# CPU_Control.net
KiCad netlist of a schematic drawn in Altium Designer
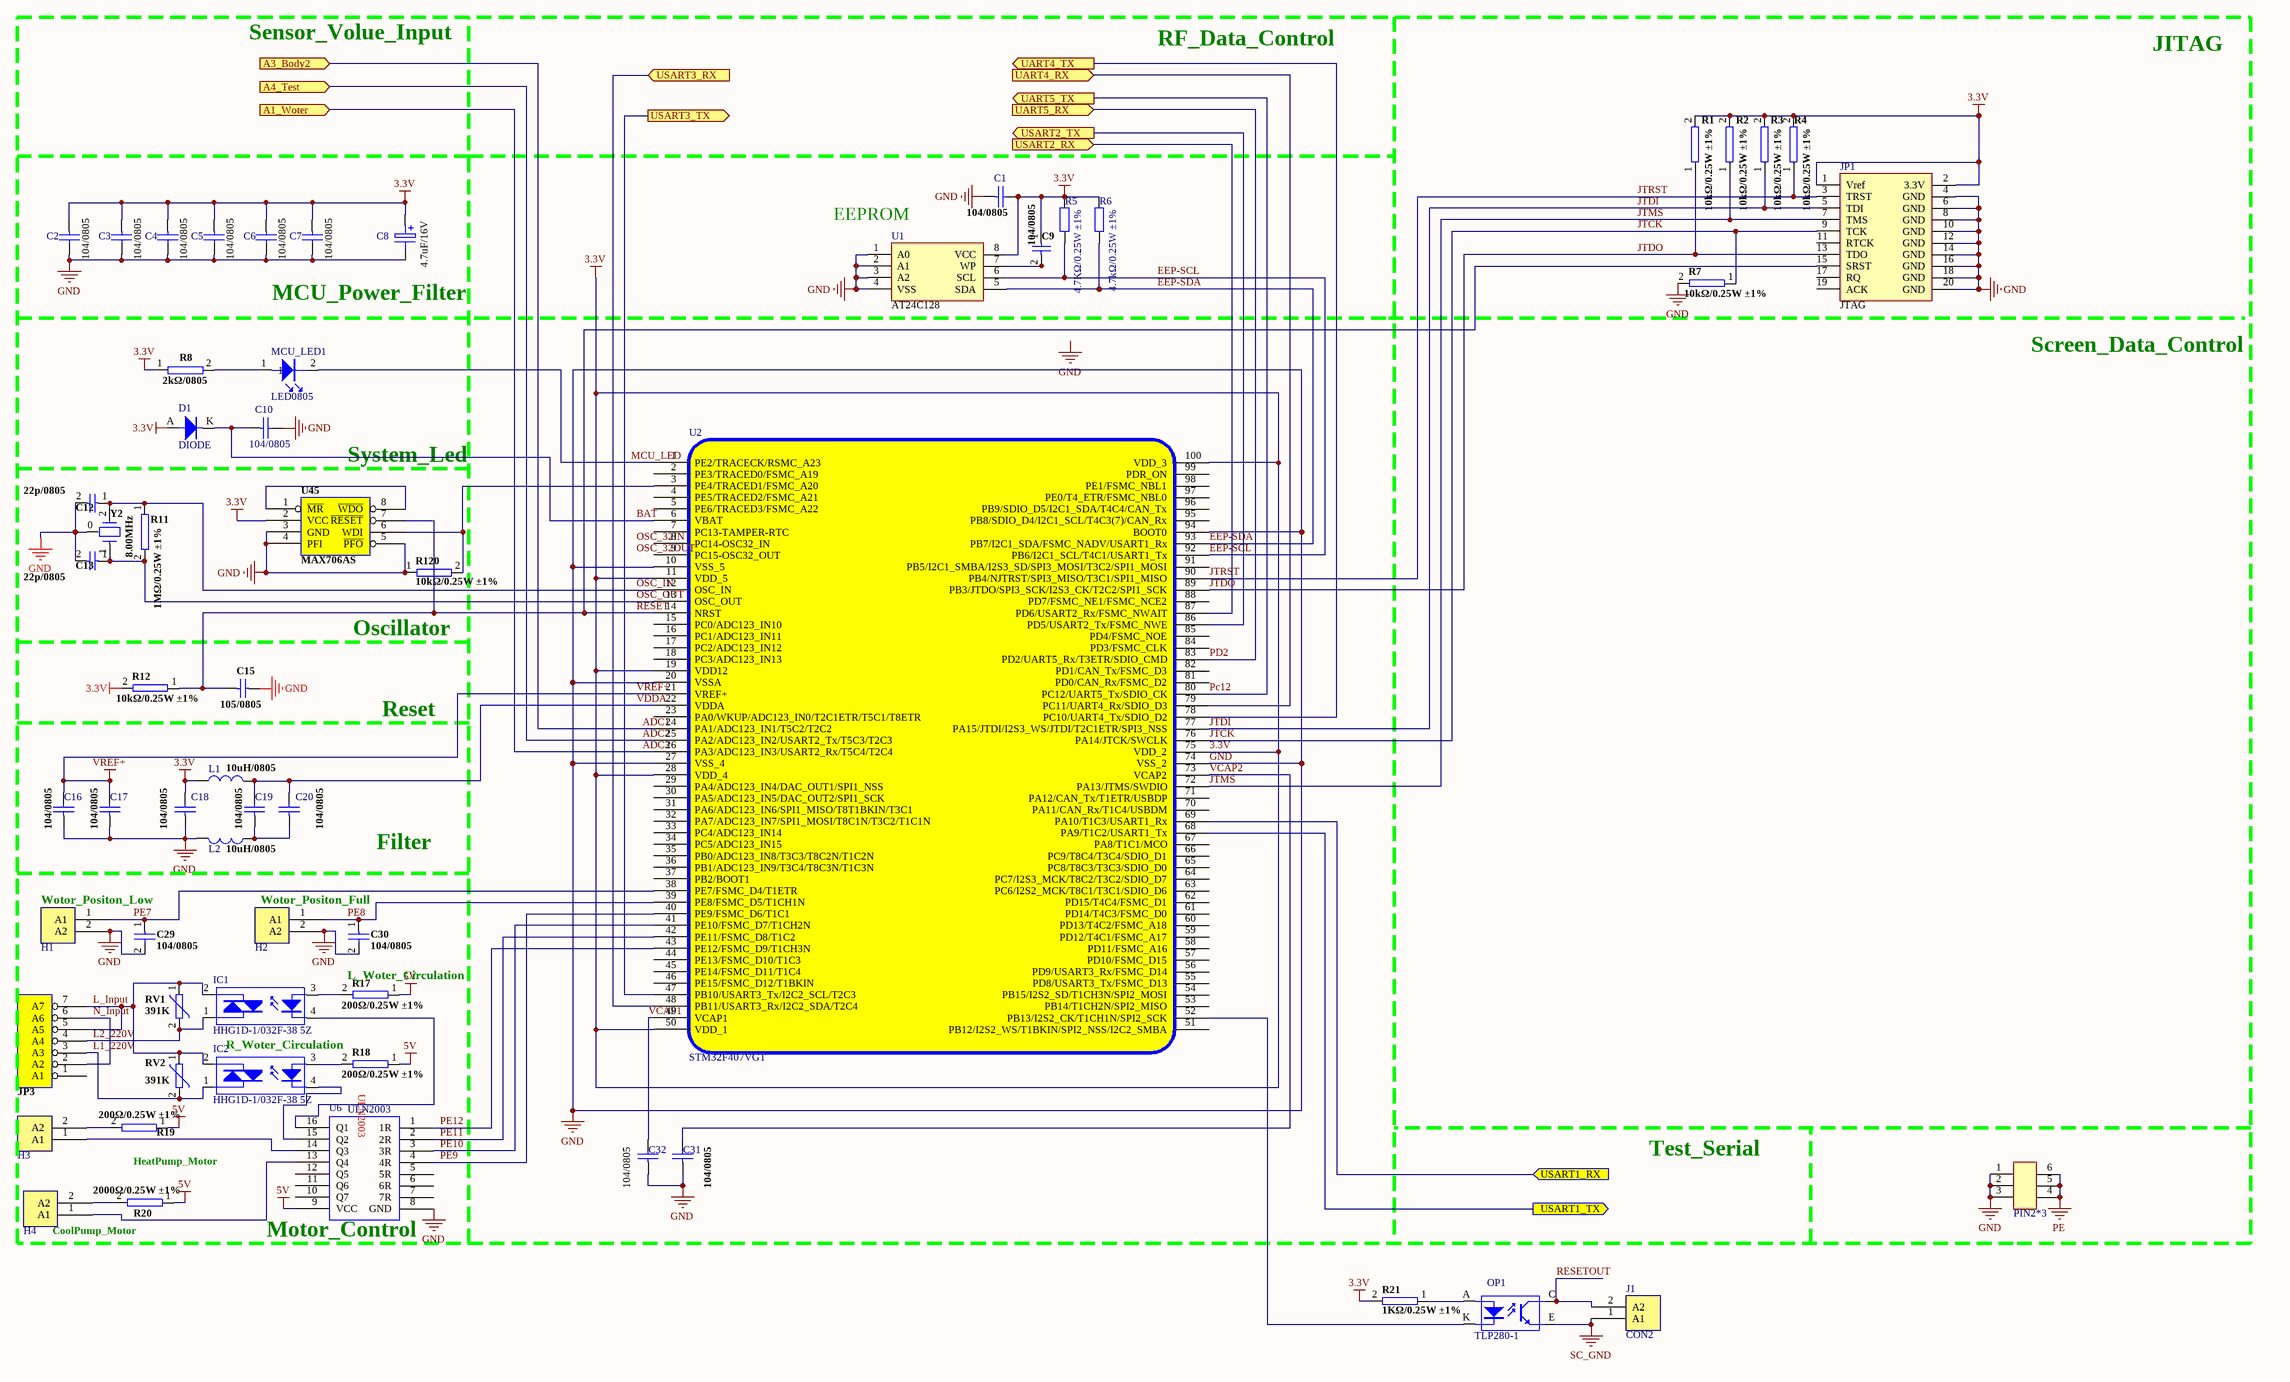
[diagram p0: CPU_Control.SchDoc]

(export (version "E")
  (design (tool "Eeschema 10.0.6"))
  (components
    (comp (ref "C1")
      (value "104/0805")
      (footprint "C0805")
      (description "贴片电容 104/25V ±1% C0805")
      (libsource (lib "*") (part "CAP"))
    )
    (comp (ref "C2")
      (value "104/0805")
      (footprint "COOLCONTROL:C0805")
      (description "贴片电容 104/25V ±1% C0805")
      (libsource (lib "*") (part "CAP"))
    )
    (comp (ref "C3")
      (value "104/0805")
      (footprint "C0805")
      (description "贴片电容 104/25V ±1% C0805")
      (libsource (lib "*") (part "CAP"))
    )
    (comp (ref "C4")
      (value "104/0805")
      (footprint "C0805")
      (description "贴片电容 104/25V ±1% C0805")
      (libsource (lib "*") (part "CAP"))
    )
    (comp (ref "C5")
      (value "104/0805")
      (footprint "C0805")
      (description "贴片电容 104/25V ±1% C0805")
      (libsource (lib "*") (part "CAP"))
    )
    (comp (ref "C6")
      (value "104/0805")
      (footprint "C0805")
      (description "贴片电容 104/25V ±1% C0805")
      (libsource (lib "*") (part "CAP"))
    )
    (comp (ref "C7")
      (value "104/0805")
      (footprint "C0805")
      (description "贴片电容 104/25V ±1% C0805")
      (libsource (lib "*") (part "CAP"))
    )
    (comp (ref "C8")
      (value "4.7uF/16V")
      (footprint "CAP5X5")
      (description "贴片钽电容 4.7uF/16V ±10% CAP5X5")
      (libsource (lib "*") (part "ELECTRO1"))
    )
    (comp (ref "C9")
      (value "104/0805")
      (footprint "C0805")
      (description "贴片电容 104/25V ±1% C0805")
      (libsource (lib "") (part "CAP_3"))
    )
    (comp (ref "C10")
      (value "104/0805")
      (footprint "C0805")
      (description "贴片电容 104/50V ±1% C0805")
      (libsource (lib "*") (part "CAP"))
    )
    (comp (ref "C12")
      (value "22p/0805")
      (footprint "C0805")
      (description "贴片电容 22pF/25V ±1% C0805")
      (libsource (lib "") (part "CAP_3"))
    )
    (comp (ref "C13")
      (value "22p/0805")
      (footprint "C0805")
      (description "贴片电容 22pF/25V ±1% C0805")
      (libsource (lib "") (part "CAP_3"))
    )
    (comp (ref "C15")
      (value "105/0805")
      (footprint "C0805")
      (description "贴片电容 105/25V ±1% C0805")
      (fields (field (name "PUBLISHER") "Altium Limited"))
      (libsource (lib "") (part "CAP_1"))
    )
    (comp (ref "C16")
      (value "104/0805")
      (footprint "C0805")
      (description "贴片电容 104/25V ±1% C0805")
      (libsource (lib "*") (part "CAP"))
    )
    (comp (ref "C17")
      (value "104/0805")
      (footprint "C0805")
      (description "贴片电容 104/25V ±1% C0805")
      (libsource (lib "*") (part "CAP"))
    )
    (comp (ref "C18")
      (value "104/0805")
      (footprint "C0805")
      (description "贴片电容 104/25V ±1% C0805")
      (libsource (lib "*") (part "CAP"))
    )
    (comp (ref "C19")
      (value "104/0805")
      (footprint "C0805")
      (description "贴片电容 104/25V ±1% C0805")
      (libsource (lib "*") (part "CAP"))
    )
    (comp (ref "C20")
      (value "104/0805")
      (footprint "C0805")
      (description "贴片电容 104/25V ±1% C0805")
      (libsource (lib "*") (part "CAP"))
    )
    (comp (ref "C29")
      (value "104/0805")
      (footprint "C0805")
      (description "贴片电容 104/25V ±1% C0805")
      (libsource (lib "") (part "CAP_2"))
    )
    (comp (ref "C30")
      (value "104/0805")
      (footprint "C0805")
      (description "贴片电容 104/25V ±1% C0805")
      (libsource (lib "") (part "CAP_2"))
    )
    (comp (ref "C31")
      (value "104/0805")
      (footprint "C0805")
      (description "贴片电容 104/25V ±1% C0805")
      (libsource (lib "*") (part "CAP"))
    )
    (comp (ref "C32")
      (value "104/0805")
      (footprint "C0805")
      (description "贴片电容 104/25V ±1% C0805")
      (libsource (lib "*") (part "CAP"))
    )
    (comp (ref "D1")
      (value "DIODE")
      (footprint "SOD123")
      (description "高速开关二极管 IN4148 1V 150mA SOD123")
      (libsource (lib "COOLCONTROL") (part "DIODE"))
    )
    (comp (ref "H1")
      (value "L_Wotor_Port")
      (footprint "XH2")
      (description "插座式端子 XH2.54-2P 250V(DC/AC) 3A")
      (libsource (lib "") (part "CON2_2"))
    )
    (comp (ref "H2")
      (value "F_Wotor_Port")
      (footprint "XH2")
      (description "插座式端子 XH2.54-2P 250V(DC/AC) 3A")
      (libsource (lib "") (part "CON2_2"))
    )
    (comp (ref "H3")
      (value "Heat_Port")
      (footprint "XH2")
      (description "插座式端子 XH2.54-2P 250V(DC/AC) 3A")
      (libsource (lib "COOLCONTROL") (part "CON2"))
    )
    (comp (ref "H4")
      (value "Cool_Port")
      (footprint "XH2")
      (description "插座式端子 XH2.54-2P 250V(DC/AC) 3A")
      (libsource (lib "COOLCONTROL") (part "CON2"))
    )
    (comp (ref "IC1")
      (value "HHG1D-1/032F-38 5Z")
      (footprint "HHG1-REALY")
      (description "固态继电器 HHG1D-1/032F-38 5Z HHG1-REALY")
      (libsource (lib "COOLCONTROL") (part "OPTOTRIAC"))
    )
    (comp (ref "IC2")
      (value "HHG1D-1/032F-38 5Z")
      (footprint "HHG1-REALY")
      (description "固态继电器 HHG1D-1/032F-38 5Z HHG1-REALY")
      (libsource (lib "COOLCONTROL") (part "OPTOTRIAC"))
    )
    (comp (ref "J1")
      (value "CON2")
      (footprint "COOLCONTROL:2Pin-2.54")
      (description "单排排针（2针）2.54mm 2Pin-2.54")
      (libsource (lib "") (part "CON2_1"))
    )
    (comp (ref "JP1")
      (value "JTAG")
      (footprint "IDC20_A")
      (description "双排排针（10针）2.54mm IDC20_A")
      (libsource (lib "COOLCONTROL") (part "JTAG20"))
    )
    (comp (ref "JP3")
      (value "L_N_Port")
      (footprint "HEADER1x7")
      (description "接线端子 22-12AWG 300V 20A 间距8.5mm/HEADER1x7")
      (libsource (lib "*") (part "CON7"))
    )
    (comp (ref "L1")
      (value "10uH/0805")
      (footprint "L0805")
      (description "贴片电感 10uH/L0805/0.25W ±10%")
      (libsource (lib "*") (part "INDUCTOR1"))
    )
    (comp (ref "L2")
      (value "10uH/0805")
      (footprint "L0805")
      (description "贴片电感 10uH/L0805/0.25W ±10%")
      (libsource (lib "") (part "INDUCTOR1_1"))
    )
    (comp (ref "MCU_LED1")
      (value "LED0805")
      (footprint "LED_0805")
      (description "贴片LED灯 2.0V 20mA 蓝色 LED_0805")
      (libsource (lib "COOLCONTROL") (part "LED0805"))
    )
    (comp (ref "OP1")
      (value "TLP280-1")
      (footprint "SOP4")
      (description "光耦 TLP280-1 SOP4")
      (libsource (lib "COOLCONTROL") (part "TLP521"))
    )
    (comp (ref "PE1")
      (value "PIN2*3")
      (footprint "IDC2x3")
      (description "双排排针（3针）2.54mm IDC2x3")
      (libsource (lib "COOLCONTROL") (part "PIN2*3"))
    )
    (comp (ref "R1")
      (value "10kΩ/0.25W ±1%")
      (footprint "R0805")
      (description "贴片电阻 10kΩ 0.25W ±1% R0805")
      (libsource (lib "") (part "RES2_1"))
    )
    (comp (ref "R2")
      (value "10kΩ/0.25W ±1%")
      (footprint "R0805")
      (description "贴片电阻 10kΩ 0.25W ±1% R0805")
      (libsource (lib "") (part "RES2_1"))
    )
    (comp (ref "R3")
      (value "10kΩ/0.25W ±1%")
      (footprint "R0805")
      (description "贴片电阻 10kΩ 0.25W ±1% R0805")
      (libsource (lib "") (part "RES2_1"))
    )
    (comp (ref "R4")
      (value "10kΩ/0.25W ±1%")
      (footprint "R0805")
      (description "贴片电阻 10kΩ 0.25W ±1% R0805")
      (libsource (lib "") (part "RES2_1"))
    )
    (comp (ref "R5")
      (value "4.7KΩ/0.25W ±1%")
      (footprint "R0805")
      (description "贴片电阻 4.7kΩ 0.25W ±1% R0805")
      (fields (field (name "PUBLISHER") "Altium Limited"))
      (libsource (lib "*") (part "Res2"))
    )
    (comp (ref "R6")
      (value "4.7kΩ/0.25W ±1%")
      (footprint "R0805")
      (description "贴片电阻 4.7kΩ/0.25W ±1% R0805")
      (fields (field (name "PUBLISHER") "Altium Limited"))
      (libsource (lib "*") (part "Res2"))
    )
    (comp (ref "R7")
      (value "10kΩ/0.25W ±1%")
      (footprint "R0805")
      (description "贴片电阻 10kΩ 0.25W ±1% R0805")
      (libsource (lib "") (part "RES2_1"))
    )
    (comp (ref "R8")
      (value "2kΩ/0805")
      (footprint "R0805")
      (description "贴片电阻 2kΩ 0.25W ±1% R0805")
      (libsource (lib "*") (part "RES2"))
    )
    (comp (ref "R11")
      (value "1MΩ/0.25W ±1%")
      (footprint "R0805")
      (description "贴片电阻 1MΩ 0.25W ±1% R0805")
      (libsource (lib "*") (part "RES2"))
    )
    (comp (ref "R12")
      (value "10kΩ/0.25W ±1%")
      (footprint "R0805")
      (description "贴片电阻 10kΩ 0.25W ±1% R0805")
      (libsource (lib "*") (part "RES2"))
    )
    (comp (ref "R17")
      (value "200Ω/0.25W ±1%")
      (footprint "R0805")
      (description "贴片电阻 200Ω 0.25W ±1% R0805")
      (libsource (lib "") (part "RES2_1"))
    )
    (comp (ref "R18")
      (value "200Ω/0.25W ±1%")
      (footprint "R0805")
      (description "贴片电阻 200Ω 0.25W ±1% R0805")
      (libsource (lib "") (part "RES2_1"))
    )
    (comp (ref "R19")
      (value "200Ω/0.25W ±1%")
      (footprint "R0805")
      (description "贴片电阻 200Ω 0.25W ±1% R0805")
      (libsource (lib "") (part "RES2_1"))
    )
    (comp (ref "R20")
      (value "2000Ω/0.25W ±1%")
      (footprint "R0805")
      (description "贴片电阻 2kΩ 0.25W ±1% R0805")
      (libsource (lib "") (part "RES2_1"))
    )
    (comp (ref "R21")
      (value "1KΩ/0.25W ±1%")
      (footprint "R0805")
      (description "贴片电阻 1kΩ 0.25W ±1% R0805")
      (libsource (lib "COOLCONTROL") (part "RES2"))
    )
    (comp (ref "R120")
      (value "10kΩ/0.25W ±1%")
      (footprint "R0805")
      (description "贴片电阻 10kΩ 0.25W ±1% R0805")
      (libsource (lib "*") (part "RES2"))
    )
    (comp (ref "RV1")
      (value "391K")
      (footprint "RV0.3")
      (description "压敏电阻 391K 340V ±10% RV0.3")
      (libsource (lib "*") (part "VARISTOR"))
    )
    (comp (ref "RV2")
      (value "391K")
      (footprint "RV0.3")
      (description "压敏电阻 391K 340V ±10% RV0.3")
      (libsource (lib "*") (part "VARISTOR"))
    )
    (comp (ref "U1")
      (value "AT24C128")
      (footprint "SO-8")
      (description "存储器 EEPROM 芯片 AT24C128 SO-8")
      (libsource (lib "*") (part "24WC02"))
    )
    (comp (ref "U2")
      (value "STM32F407VGT")
      (footprint "LQFP-100")
      (description "STM32F407单片机 STM32F407VGT LQFP-100")
      (libsource (lib "COOLCONTROL") (part "STM32F407VGT"))
    )
    (comp (ref "U6")
      (value "ULN2003")
      (footprint "SOIC-16")
      (description "达林顿三极管集成IC ULN2003 SOIC-16")
      (libsource (lib "COOLCONTROL") (part "ULN2003"))
    )
    (comp (ref "U45")
      (value "MAX706AS")
      (footprint "SO-8")
      (description "看门狗IC MAX706AS SO-8")
      (libsource (lib "*") (part "MAX705CPA"))
    )
    (comp (ref "Y2")
      (value "8.00MHz")
      (footprint "XTAL_SOCKET")
      (description "晶振 8.00MHz XTAL_SOCKET")
      (libsource (lib "COOLCONTROL") (part "CRYSTAL"))
    )
  )
  (nets
    (net (code "1") (name "/ADC1") (class "Default")
      (node (ref "U2") (pin "24") (pinfunction "PA1/ADC123_IN1/T5C2/T2C2_24") (pintype "passive"))
    )
    (net (code "2") (name "/ADC2") (class "Default")
      (node (ref "U2") (pin "25") (pinfunction "PA2/ADC123_IN2/USART2_Tx/T5C3/T2C3_25") (pintype "passive"))
    )
    (net (code "3") (name "/ADC3") (class "Default")
      (node (ref "U2") (pin "26") (pinfunction "PA3/ADC123_IN3/USART2_Rx/T5C4/T2C4_26") (pintype "passive"))
    )
    (net (code "4") (name "/BAT") (class "Default")
      (node (ref "C10") (pin "1") (pinfunction "1_1") (pintype "passive"))
      (node (ref "D1") (pin "K") (pinfunction "K_K") (pintype "passive"))
      (node (ref "U2") (pin "6") (pinfunction "VBAT_6") (pintype "passive"))
    )
    (net (code "5") (name "/EEP-SCL") (class "Default")
      (node (ref "R5") (pin "1") (pinfunction "1_1") (pintype "passive"))
      (node (ref "U1") (pin "6") (pinfunction "SCL_6") (pintype "passive"))
      (node (ref "U2") (pin "92") (pinfunction "PB6/I2C1_SCL/T4C1/USART1_Tx_92") (pintype "passive"))
    )
    (net (code "6") (name "/EEP-SDA") (class "Default")
      (node (ref "R6") (pin "1") (pinfunction "1_1") (pintype "passive"))
      (node (ref "U1") (pin "5") (pinfunction "SDA_5") (pintype "passive"))
      (node (ref "U2") (pin "93") (pinfunction "PB7/I2C1_SDA/FSMC_NADV/USART1_Rx_93") (pintype "passive"))
    )
    (net (code "7") (name "/JTCK") (class "Default")
      (node (ref "JP1") (pin "9") (pinfunction "TCK_9") (pintype "passive"))
      (node (ref "R7") (pin "1") (pintype "passive"))
      (node (ref "U2") (pin "76") (pinfunction "PA14/JTCK/SWCLK_76") (pintype "passive"))
    )
    (net (code "8") (name "/JTDI") (class "Default")
      (node (ref "JP1") (pin "5") (pinfunction "TDI_5") (pintype "passive"))
      (node (ref "R3") (pin "1") (pintype "passive"))
      (node (ref "U2") (pin "77") (pinfunction "PA15/JTDI/I2S3_WS/JTDI/T2C1ETR/SPI3_NSS_77") (pintype "passive"))
    )
    (net (code "9") (name "/JTDO") (class "Default")
      (node (ref "JP1") (pin "13") (pinfunction "TDO_13") (pintype "passive"))
      (node (ref "R1") (pin "1") (pintype "passive"))
      (node (ref "U2") (pin "89") (pinfunction "PB3/JTDO/SPI3_SCK/I2S3_CK/T2C2/SPI1_SCK_89") (pintype "passive"))
    )
    (net (code "10") (name "/JTMS") (class "Default")
      (node (ref "JP1") (pin "7") (pinfunction "TMS_7") (pintype "passive"))
      (node (ref "R2") (pin "1") (pintype "passive"))
      (node (ref "U2") (pin "72") (pinfunction "PA13/JTMS/SWDIO_72") (pintype "passive"))
    )
    (net (code "11") (name "/JTRST") (class "Default")
      (node (ref "JP1") (pin "3") (pinfunction "TRST_3") (pintype "passive"))
      (node (ref "R4") (pin "1") (pintype "passive"))
      (node (ref "U2") (pin "90") (pinfunction "PB4/NJTRST/SPI3_MISO/T3C1/SPI1_MISO_90") (pintype "passive"))
    )
    (net (code "12") (name "/L1_220V") (class "Default")
      (node (ref "IC2") (pin "1") (pintype "passive"))
      (node (ref "JP3") (pin "3") (pinfunction "A3_3") (pintype "passive"))
      (node (ref "RV2") (pin "2") (pintype "passive"))
    )
    (net (code "13") (name "/L2_220V") (class "Default")
      (node (ref "IC1") (pin "1") (pintype "passive"))
      (node (ref "JP3") (pin "4") (pinfunction "A4_4") (pintype "passive"))
      (node (ref "RV1") (pin "2") (pintype "passive"))
    )
    (net (code "14") (name "/L_Input") (class "Default")
      (node (ref "IC1") (pin "2") (pintype "passive"))
      (node (ref "IC2") (pin "2") (pintype "passive"))
      (node (ref "JP3") (pin "5") (pinfunction "A5_5") (pintype "passive"))
      (node (ref "JP3") (pin "7") (pinfunction "A7_7") (pintype "passive"))
      (node (ref "RV1") (pin "1") (pintype "passive"))
      (node (ref "RV2") (pin "1") (pintype "passive"))
    )
    (net (code "15") (name "/MCU_LED") (class "Default")
      (node (ref "MCU_LED1") (pin "2") (pinfunction "2_2") (pintype "passive"))
      (node (ref "U2") (pin "1") (pinfunction "PE2/TRACECK/RSMC_A23_1") (pintype "passive"))
    )
    (net (code "16") (name "/N_Input") (class "Default")
      (node (ref "JP3") (pin "2") (pinfunction "A2_2") (pintype "passive"))
      (node (ref "JP3") (pin "6") (pinfunction "A6_6") (pintype "passive"))
    )
    (net (code "19") (name "/OSC_IN") (class "Default")
      (node (ref "C12") (pin "1") (pintype "passive"))
      (node (ref "R11") (pin "1") (pintype "passive"))
      (node (ref "U2") (pin "12") (pinfunction "OSC_IN_12") (pintype "passive"))
      (node (ref "Y2") (pin "2") (pintype "passive"))
    )
    (net (code "20") (name "/OSC_OUT") (class "Default")
      (node (ref "C13") (pin "1") (pintype "passive"))
      (node (ref "R11") (pin "2") (pintype "passive"))
      (node (ref "U2") (pin "13") (pinfunction "OSC_OUT_13") (pintype "passive"))
      (node (ref "Y2") (pin "1") (pintype "passive"))
    )
    (net (code "21") (name "/PD2") (class "Default")
      (node (ref "U2") (pin "83") (pinfunction "PD2/UART5_Rx/T3ETR/SDIO_CMD_83") (pintype "passive"))
    )
    (net (code "22") (name "/PE7") (class "Default")
      (node (ref "C29") (pin "1") (pintype "passive"))
      (node (ref "H1") (pin "1") (pinfunction "A1_1") (pintype "passive"))
      (node (ref "U2") (pin "38") (pinfunction "PE7/FSMC_D4/T1ETR_38") (pintype "passive"))
    )
    (net (code "23") (name "/PE8") (class "Default")
      (node (ref "C30") (pin "1") (pintype "passive"))
      (node (ref "H2") (pin "1") (pinfunction "A1_1") (pintype "passive"))
      (node (ref "U2") (pin "39") (pinfunction "PE8/FSMC_D5/T1CH1N_39") (pintype "passive"))
    )
    (net (code "24") (name "/PE9") (class "Default")
      (node (ref "U2") (pin "40") (pinfunction "PE9/FSMC_D6/T1C1_40") (pintype "passive"))
      (node (ref "U6") (pin "4") (pinfunction "4R_4") (pintype "passive"))
    )
    (net (code "25") (name "/PE10") (class "Default")
      (node (ref "U2") (pin "41") (pinfunction "PE10/FSMC_D7/T1CH2N_41") (pintype "passive"))
      (node (ref "U6") (pin "3") (pinfunction "3R_3") (pintype "passive"))
    )
    (net (code "26") (name "/PE11") (class "Default")
      (node (ref "U2") (pin "42") (pinfunction "PE11/FSMC_D8/T1C2_42") (pintype "passive"))
      (node (ref "U6") (pin "2") (pinfunction "2R_2") (pintype "passive"))
    )
    (net (code "27") (name "/PE12") (class "Default")
      (node (ref "U2") (pin "43") (pinfunction "PE12/FSMC_D9/T1CH3N_43") (pintype "passive"))
      (node (ref "U6") (pin "1") (pinfunction "1R_1") (pintype "passive"))
    )
    (net (code "28") (name "/Pc12") (class "Default")
      (node (ref "U2") (pin "80") (pinfunction "PC12/UART5_Tx/SDIO_CK_80") (pintype "passive"))
    )
    (net (code "29") (name "/RESET") (class "Default")
      (node (ref "C15") (pin "2") (pinfunction "2_2") (pintype "passive"))
      (node (ref "JP1") (pin "15") (pinfunction "SRST_15") (pintype "passive"))
      (node (ref "R12") (pin "1") (pintype "passive"))
      (node (ref "U2") (pin "14") (pinfunction "NRST_14") (pintype "passive"))
      (node (ref "U45") (pin "7") (pinfunction "~{RESET}_7") (pintype "passive"))
    )
    (net (code "30") (name "/RESETOUT") (class "Default")
      (node (ref "J1") (pin "2") (pinfunction "A2_2") (pintype "passive"))
      (node (ref "OP1") (pin "C") (pintype "passive"))
    )
    (net (code "31") (name "/UART4_RX") (class "Default")
      (node (ref "U2") (pin "79") (pinfunction "PC11/UART4_Rx/SDIO_D3_79") (pintype "passive"))
    )
    (net (code "32") (name "/UART4_TX") (class "Default")
      (node (ref "U2") (pin "78") (pinfunction "PC10/UART4_Tx/SDIO_D2_78") (pintype "passive"))
    )
    (net (code "33") (name "/USART1_RX") (class "Default")
      (node (ref "U2") (pin "69") (pinfunction "PA10/T1C3/USART1_Rx_69") (pintype "passive"))
    )
    (net (code "34") (name "/USART1_TX") (class "Default")
      (node (ref "U2") (pin "68") (pinfunction "PA9/T1C2/USART1_Tx_68") (pintype "passive"))
    )
    (net (code "35") (name "/USART2_RX") (class "Default")
      (node (ref "U2") (pin "87") (pinfunction "PD6/USART2_Rx/FSMC_NWAIT_87") (pintype "passive"))
    )
    (net (code "36") (name "/USART2_TX") (class "Default")
      (node (ref "U2") (pin "86") (pinfunction "PD5/USART2_Tx/FSMC_NWE_86") (pintype "passive"))
    )
    (net (code "37") (name "/USART3_RX") (class "Default")
      (node (ref "U2") (pin "48") (pinfunction "PB11/USART3_Rx/I2C2_SDA/T2C4_48") (pintype "passive"))
    )
    (net (code "38") (name "/USART3_TX") (class "Default")
      (node (ref "U2") (pin "47") (pinfunction "PB10/USART3_Tx/I2C2_SCL/T2C3_47") (pintype "passive"))
    )
    (net (code "39") (name "/VCAP1") (class "Default")
      (node (ref "C32") (pin "2") (pinfunction "2_2") (pintype "passive"))
      (node (ref "U2") (pin "49") (pinfunction "VCAP1_49") (pintype "passive"))
    )
    (net (code "40") (name "/VCAP2") (class "Default")
      (node (ref "C31") (pin "2") (pinfunction "2_2") (pintype "passive"))
      (node (ref "U2") (pin "73") (pinfunction "VCAP2_73") (pintype "passive"))
    )
    (net (code "41") (name "/VDDA") (class "Default")
      (node (ref "C19") (pin "2") (pinfunction "2_2") (pintype "passive"))
      (node (ref "C20") (pin "2") (pinfunction "2_2") (pintype "passive"))
      (node (ref "L1") (pin "2") (pinfunction "2_2") (pintype "passive"))
      (node (ref "U2") (pin "22") (pinfunction "VDDA_22") (pintype "passive"))
    )
    (net (code "42") (name "3.3V") (class "Default")
      (node (ref "C1") (pin "2") (pinfunction "2_2") (pintype "passive"))
      (node (ref "C18") (pin "2") (pinfunction "2_2") (pintype "passive"))
      (node (ref "C2") (pin "1") (pinfunction "1_1") (pintype "passive"))
      (node (ref "C3") (pin "1") (pinfunction "1_1") (pintype "passive"))
      (node (ref "C4") (pin "1") (pinfunction "1_1") (pintype "passive"))
      (node (ref "C5") (pin "1") (pinfunction "1_1") (pintype "passive"))
      (node (ref "C6") (pin "1") (pinfunction "1_1") (pintype "passive"))
      (node (ref "C7") (pin "1") (pinfunction "1_1") (pintype "passive"))
      (node (ref "C8") (pin "1") (pinfunction "1_1") (pintype "passive"))
      (node (ref "C9") (pin "1") (pintype "passive"))
      (node (ref "D1") (pin "A") (pinfunction "A_A") (pintype "passive"))
      (node (ref "JP1") (pin "1") (pinfunction "Vref_1") (pintype "passive"))
      (node (ref "JP1") (pin "2") (pinfunction "3.3V_2") (pintype "passive"))
      (node (ref "L1") (pin "1") (pinfunction "1_1") (pintype "passive"))
      (node (ref "R1") (pin "2") (pintype "passive"))
      (node (ref "R12") (pin "2") (pintype "passive"))
      (node (ref "R2") (pin "2") (pintype "passive"))
      (node (ref "R21") (pin "2") (pintype "passive"))
      (node (ref "R3") (pin "2") (pintype "passive"))
      (node (ref "R4") (pin "2") (pintype "passive"))
      (node (ref "R5") (pin "2") (pinfunction "2_2") (pintype "passive"))
      (node (ref "R6") (pin "2") (pinfunction "2_2") (pintype "passive"))
      (node (ref "R8") (pin "1") (pintype "passive"))
      (node (ref "U1") (pin "8") (pinfunction "VCC_8") (pintype "passive"))
      (node (ref "U2") (pin "100") (pinfunction "VDD_3_100") (pintype "passive"))
      (node (ref "U2") (pin "11") (pinfunction "VDD_5_11") (pintype "passive"))
      (node (ref "U2") (pin "19") (pinfunction "VDD12_19") (pintype "passive"))
      (node (ref "U2") (pin "28") (pinfunction "VDD_4_28") (pintype "passive"))
      (node (ref "U2") (pin "50") (pinfunction "VDD_1_50") (pintype "passive"))
      (node (ref "U2") (pin "75") (pinfunction "VDD_2_75") (pintype "passive"))
      (node (ref "U45") (pin "2") (pinfunction "VCC_2") (pintype "passive"))
    )
    (net (code "43") (name "5V") (class "Default")
      (node (ref "R17") (pin "1") (pintype "passive"))
      (node (ref "R18") (pin "1") (pintype "passive"))
      (node (ref "R19") (pin "1") (pintype "passive"))
      (node (ref "R20") (pin "1") (pintype "passive"))
      (node (ref "U6") (pin "9") (pinfunction "VCC_9") (pintype "passive"))
    )
    (net (code "44") (name "GND") (class "Default")
      (node (ref "C1") (pin "1") (pinfunction "1_1") (pintype "passive"))
      (node (ref "C10") (pin "2") (pinfunction "2_2") (pintype "passive"))
      (node (ref "C12") (pin "2") (pintype "passive"))
      (node (ref "C13") (pin "2") (pintype "passive"))
      (node (ref "C15") (pin "1") (pinfunction "1_1") (pintype "passive"))
      (node (ref "C16") (pin "1") (pinfunction "1_1") (pintype "passive"))
      (node (ref "C17") (pin "1") (pinfunction "1_1") (pintype "passive"))
      (node (ref "C18") (pin "1") (pinfunction "1_1") (pintype "passive"))
      (node (ref "C2") (pin "2") (pinfunction "2_2") (pintype "passive"))
      (node (ref "C29") (pin "2") (pintype "passive"))
      (node (ref "C3") (pin "2") (pinfunction "2_2") (pintype "passive"))
      (node (ref "C30") (pin "2") (pintype "passive"))
      (node (ref "C31") (pin "1") (pinfunction "1_1") (pintype "passive"))
      (node (ref "C32") (pin "1") (pinfunction "1_1") (pintype "passive"))
      (node (ref "C4") (pin "2") (pinfunction "2_2") (pintype "passive"))
      (node (ref "C5") (pin "2") (pinfunction "2_2") (pintype "passive"))
      (node (ref "C6") (pin "2") (pinfunction "2_2") (pintype "passive"))
      (node (ref "C7") (pin "2") (pinfunction "2_2") (pintype "passive"))
      (node (ref "C8") (pin "2") (pinfunction "2_2") (pintype "passive"))
      (node (ref "H1") (pin "2") (pinfunction "A2_2") (pintype "passive"))
      (node (ref "H2") (pin "2") (pinfunction "A2_2") (pintype "passive"))
      (node (ref "JP1") (pin "10") (pinfunction "GND_10") (pintype "passive"))
      (node (ref "JP1") (pin "12") (pinfunction "GND_12") (pintype "passive"))
      (node (ref "JP1") (pin "14") (pinfunction "GND_14") (pintype "passive"))
      (node (ref "JP1") (pin "16") (pinfunction "GND_16") (pintype "passive"))
      (node (ref "JP1") (pin "18") (pinfunction "GND_18") (pintype "passive"))
      (node (ref "JP1") (pin "20") (pinfunction "GND_20") (pintype "passive"))
      (node (ref "JP1") (pin "4") (pinfunction "GND_4") (pintype "passive"))
      (node (ref "JP1") (pin "6") (pinfunction "GND_6") (pintype "passive"))
      (node (ref "JP1") (pin "8") (pinfunction "GND_8") (pintype "passive"))
      (node (ref "L2") (pin "1") (pinfunction "1_1") (pintype "passive"))
      (node (ref "PE1") (pin "1") (pintype "passive"))
      (node (ref "PE1") (pin "2") (pintype "passive"))
      (node (ref "PE1") (pin "3") (pintype "passive"))
      (node (ref "R120") (pin "1") (pintype "passive"))
      (node (ref "R7") (pin "2") (pintype "passive"))
      (node (ref "U1") (pin "1") (pinfunction "A0_1") (pintype "passive"))
      (node (ref "U1") (pin "2") (pinfunction "A1_2") (pintype "passive"))
      (node (ref "U1") (pin "3") (pinfunction "A2_3") (pintype "passive"))
      (node (ref "U1") (pin "4") (pinfunction "VSS_4") (pintype "passive"))
      (node (ref "U2") (pin "10") (pinfunction "VSS_5_10") (pintype "passive"))
      (node (ref "U2") (pin "20") (pinfunction "VSSA_20") (pintype "passive"))
      (node (ref "U2") (pin "27") (pinfunction "VSS_4_27") (pintype "passive"))
      (node (ref "U2") (pin "74") (pinfunction "VSS_2_74") (pintype "passive"))
      (node (ref "U2") (pin "94") (pinfunction "BOOT0_94") (pintype "passive"))
      (node (ref "U45") (pin "3") (pinfunction "GND_3") (pintype "passive"))
      (node (ref "U45") (pin "4") (pinfunction "PFI_4") (pintype "passive"))
      (node (ref "U45") (pin "5") (pinfunction "~{PFO}_5") (pintype "passive"))
      (node (ref "U6") (pin "8") (pinfunction "GND_8") (pintype "passive"))
      (node (ref "Y2") (pin "0") (pintype "passive"))
    )
    (net (code "45") (name "Net-(C19-Pad1)") (class "Default")
      (node (ref "C19") (pin "1") (pinfunction "1_1") (pintype "passive"))
      (node (ref "C20") (pin "1") (pinfunction "1_1") (pintype "passive"))
      (node (ref "L2") (pin "2") (pinfunction "2_2") (pintype "passive"))
    )
    (net (code "46") (name "Net-(H3-A1)") (class "Default")
      (node (ref "H3") (pin "1") (pinfunction "A1_1") (pintype "passive"))
      (node (ref "U6") (pin "14") (pinfunction "Q3_14") (pintype "passive"))
    )
    (net (code "47") (name "Net-(H3-A2)") (class "Default")
      (node (ref "H3") (pin "2") (pinfunction "A2_2") (pintype "passive"))
      (node (ref "R19") (pin "2") (pintype "passive"))
    )
    (net (code "48") (name "Net-(H4-A1)") (class "Default")
      (node (ref "H4") (pin "1") (pinfunction "A1_1") (pintype "passive"))
      (node (ref "U6") (pin "13") (pinfunction "Q4_13") (pintype "passive"))
    )
    (net (code "49") (name "Net-(H4-A2)") (class "Default")
      (node (ref "H4") (pin "2") (pinfunction "A2_2") (pintype "passive"))
      (node (ref "R20") (pin "2") (pintype "passive"))
    )
    (net (code "50") (name "Net-(IC1-Pad3)") (class "Default")
      (node (ref "IC1") (pin "3") (pintype "passive"))
      (node (ref "R17") (pin "2") (pintype "passive"))
    )
    (net (code "51") (name "Net-(IC2-Pad3)") (class "Default")
      (node (ref "IC2") (pin "3") (pintype "passive"))
      (node (ref "R18") (pin "2") (pintype "passive"))
    )
    (net (code "52") (name "Net-(MCU_LED1-Pad1)") (class "Default")
      (node (ref "MCU_LED1") (pin "1") (pinfunction "1_1") (pintype "passive"))
      (node (ref "R8") (pin "2") (pintype "passive"))
    )
    (net (code "53") (name "Net-(OP1-PadA)") (class "Default")
      (node (ref "OP1") (pin "A") (pintype "passive"))
      (node (ref "R21") (pin "1") (pintype "passive"))
    )
    (net (code "54") (name "Net-(U1-WP)") (class "Default")
      (node (ref "C9") (pin "2") (pintype "passive"))
      (node (ref "U1") (pin "7") (pinfunction "WP_7") (pintype "passive"))
    )
    (net (code "55") (name "Net-(U2-PB13{slash}I2S2_CK{slash}T1CH1N{slash}SPI2_SCK)") (class "Default")
      (node (ref "OP1") (pin "K") (pintype "passive"))
      (node (ref "U2") (pin "52") (pinfunction "PB13/I2S2_CK/T1CH1N/SPI2_SCK_52") (pintype "passive"))
    )
    (net (code "56") (name "Net-(U2-PE4{slash}TRACED1{slash}FSMC_A20)") (class "Default")
      (node (ref "R120") (pin "2") (pintype "passive"))
      (node (ref "U2") (pin "3") (pinfunction "PE4/TRACED1/FSMC_A20_3") (pintype "passive"))
      (node (ref "U45") (pin "6") (pinfunction "WDI_6") (pintype "passive"))
    )
    (net (code "57") (name "Net-(U6-Q1)") (class "Default")
      (node (ref "IC1") (pin "4") (pintype "passive"))
      (node (ref "U6") (pin "16") (pinfunction "Q1_16") (pintype "passive"))
    )
    (net (code "58") (name "Net-(U6-Q2)") (class "Default")
      (node (ref "IC2") (pin "4") (pintype "passive"))
      (node (ref "U6") (pin "15") (pinfunction "Q2_15") (pintype "passive"))
    )
    (net (code "59") (name "Net-(U45-~{MR})") (class "Default")
      (node (ref "U45") (pin "1") (pinfunction "~{MR}_1") (pintype "passive"))
      (node (ref "U45") (pin "8") (pinfunction "~{WDO}_8") (pintype "passive"))
    )
    (net (code "60") (name "PE") (class "Default")
      (node (ref "PE1") (pin "4") (pintype "passive"))
      (node (ref "PE1") (pin "5") (pintype "passive"))
      (node (ref "PE1") (pin "6") (pintype "passive"))
    )
    (net (code "61") (name "SC_GND") (class "Default")
      (node (ref "J1") (pin "1") (pinfunction "A1_1") (pintype "passive"))
      (node (ref "OP1") (pin "E") (pintype "passive"))
    )
    (net (code "62") (name "VREF+") (class "Default")
      (node (ref "C16") (pin "2") (pinfunction "2_2") (pintype "passive"))
      (node (ref "C17") (pin "2") (pinfunction "2_2") (pintype "passive"))
      (node (ref "U2") (pin "21") (pinfunction "VREF+_21") (pintype "passive"))
    )
    (net (code "63") (name "unconnected-(JP1-ACK-Pad19)") (class "Default")
      (node (ref "JP1") (pin "19") (pinfunction "ACK_19") (pintype "passive"))
    )
    (net (code "64") (name "unconnected-(JP1-RQ-Pad17)") (class "Default")
      (node (ref "JP1") (pin "17") (pinfunction "RQ_17") (pintype "passive"))
    )
    (net (code "65") (name "unconnected-(JP1-RTCK-Pad11)") (class "Default")
      (node (ref "JP1") (pin "11") (pinfunction "RTCK_11") (pintype "passive"))
    )
    (net (code "66") (name "unconnected-(JP3-A1-Pad1)") (class "Default")
      (node (ref "JP3") (pin "1") (pinfunction "A1_1") (pintype "passive"))
    )
    (net (code "67") (name "unconnected-(U2-PA0{slash}WKUP{slash}ADC123_IN0{slash}T2C1ETR{slash}T5C1{slash}T8ETR-Pad23)") (class "Default")
      (node (ref "U2") (pin "23") (pinfunction "PA0/WKUP/ADC123_IN0/T2C1ETR/T5C1/T8ETR_23") (pintype "passive"))
    )
    (net (code "68") (name "unconnected-(U2-PA4{slash}ADC123_IN4{slash}DAC_OUT1{slash}SPI1_NSS-Pad29)") (class "Default")
      (node (ref "U2") (pin "29") (pinfunction "PA4/ADC123_IN4/DAC_OUT1/SPI1_NSS_29") (pintype "passive"))
    )
    (net (code "69") (name "unconnected-(U2-PA5{slash}ADC123_IN5{slash}DAC_OUT2{slash}SPI1_SCK-Pad30)") (class "Default")
      (node (ref "U2") (pin "30") (pinfunction "PA5/ADC123_IN5/DAC_OUT2/SPI1_SCK_30") (pintype "passive"))
    )
    (net (code "70") (name "unconnected-(U2-PA6{slash}ADC123_IN6{slash}SPI1_MISO{slash}T8T1BKIN{slash}T3C1-Pad31)") (class "Default")
      (node (ref "U2") (pin "31") (pinfunction "PA6/ADC123_IN6/SPI1_MISO/T8T1BKIN/T3C1_31") (pintype "passive"))
    )
    (net (code "71") (name "unconnected-(U2-PA7{slash}ADC123_IN7{slash}SPI1_MOSI{slash}T8C1N{slash}T3C2{slash}T1C1N-Pad32)") (class "Default")
      (node (ref "U2") (pin "32") (pinfunction "PA7/ADC123_IN7/SPI1_MOSI/T8C1N/T3C2/T1C1N_32") (pintype "passive"))
    )
    (net (code "72") (name "unconnected-(U2-PA8{slash}T1C1{slash}MCO-Pad67)") (class "Default")
      (node (ref "U2") (pin "67") (pinfunction "PA8/T1C1/MCO_67") (pintype "passive"))
    )
    (net (code "73") (name "unconnected-(U2-PA11{slash}CAN_Rx{slash}T1C4{slash}USBDM-Pad70)") (class "Default")
      (node (ref "U2") (pin "70") (pinfunction "PA11/CAN_Rx/T1C4/USBDM_70") (pintype "passive"))
    )
    (net (code "74") (name "unconnected-(U2-PA12{slash}CAN_Tx{slash}T1ETR{slash}USBDP-Pad71)") (class "Default")
      (node (ref "U2") (pin "71") (pinfunction "PA12/CAN_Tx/T1ETR/USBDP_71") (pintype "passive"))
    )
    (net (code "75") (name "unconnected-(U2-PB0{slash}ADC123_IN8{slash}T3C3{slash}T8C2N{slash}T1C2N-Pad35)") (class "Default")
      (node (ref "U2") (pin "35") (pinfunction "PB0/ADC123_IN8/T3C3/T8C2N/T1C2N_35") (pintype "passive"))
    )
    (net (code "76") (name "unconnected-(U2-PB1{slash}ADC123_IN9{slash}T3C4{slash}T8C3N{slash}T1C3N-Pad36)") (class "Default")
      (node (ref "U2") (pin "36") (pinfunction "PB1/ADC123_IN9/T3C4/T8C3N/T1C3N_36") (pintype "passive"))
    )
    (net (code "77") (name "unconnected-(U2-PB2{slash}BOOT1-Pad37)") (class "Default")
      (node (ref "U2") (pin "37") (pinfunction "PB2/BOOT1_37") (pintype "passive"))
    )
    (net (code "78") (name "unconnected-(U2-PB5{slash}I2C1_SMBA{slash}I2S3_SD{slash}SPI3_MOSI{slash}T3C2{slash}SPI1_MOSI-Pad91)") (class "Default")
      (node (ref "U2") (pin "91") (pinfunction "PB5/I2C1_SMBA/I2S3_SD/SPI3_MOSI/T3C2/SPI1_MOSI_91") (pintype "passive"))
    )
    (net (code "79") (name "unconnected-(U2-PB8{slash}SDIO_D4{slash}I2C1_SCL{slash}T4C3(7){slash}CAN_Rx-Pad95)") (class "Default")
      (node (ref "U2") (pin "95") (pinfunction "PB8/SDIO_D4/I2C1_SCL/T4C3(7)/CAN_Rx_95") (pintype "passive"))
    )
    (net (code "80") (name "unconnected-(U2-PB9{slash}SDIO_D5{slash}I2C1_SDA{slash}T4C4{slash}CAN_Tx-Pad96)") (class "Default")
      (node (ref "U2") (pin "96") (pinfunction "PB9/SDIO_D5/I2C1_SDA/T4C4/CAN_Tx_96") (pintype "passive"))
    )
    (net (code "81") (name "unconnected-(U2-PB12{slash}I2S2_WS{slash}T1BKIN{slash}SPI2_NSS{slash}I2C2_SMBA-Pad51)") (class "Default")
      (node (ref "U2") (pin "51") (pinfunction "PB12/I2S2_WS/T1BKIN/SPI2_NSS/I2C2_SMBA_51") (pintype "passive"))
    )
    (net (code "82") (name "unconnected-(U2-PB14{slash}T1CH2N{slash}SPI2_MISO-Pad53)") (class "Default")
      (node (ref "U2") (pin "53") (pinfunction "PB14/T1CH2N/SPI2_MISO_53") (pintype "passive"))
    )
    (net (code "83") (name "unconnected-(U2-PB15{slash}I2S2_SD{slash}T1CH3N{slash}SPI2_MOSI-Pad54)") (class "Default")
      (node (ref "U2") (pin "54") (pinfunction "PB15/I2S2_SD/T1CH3N/SPI2_MOSI_54") (pintype "passive"))
    )
    (net (code "84") (name "unconnected-(U2-PC0{slash}ADC123_IN10-Pad15)") (class "Default")
      (node (ref "U2") (pin "15") (pinfunction "PC0/ADC123_IN10_15") (pintype "passive"))
    )
    (net (code "85") (name "unconnected-(U2-PC1{slash}ADC123_IN11-Pad16)") (class "Default")
      (node (ref "U2") (pin "16") (pinfunction "PC1/ADC123_IN11_16") (pintype "passive"))
    )
    (net (code "86") (name "unconnected-(U2-PC2{slash}ADC123_IN12-Pad17)") (class "Default")
      (node (ref "U2") (pin "17") (pinfunction "PC2/ADC123_IN12_17") (pintype "passive"))
    )
    (net (code "87") (name "unconnected-(U2-PC3{slash}ADC123_IN13-Pad18)") (class "Default")
      (node (ref "U2") (pin "18") (pinfunction "PC3/ADC123_IN13_18") (pintype "passive"))
    )
    (net (code "88") (name "unconnected-(U2-PC4{slash}ADC123_IN14-Pad33)") (class "Default")
      (node (ref "U2") (pin "33") (pinfunction "PC4/ADC123_IN14_33") (pintype "passive"))
    )
    (net (code "89") (name "unconnected-(U2-PC5{slash}ADC123_IN15-Pad34)") (class "Default")
      (node (ref "U2") (pin "34") (pinfunction "PC5/ADC123_IN15_34") (pintype "passive"))
    )
    (net (code "90") (name "unconnected-(U2-PC6{slash}I2S2_MCK{slash}T8C1{slash}T3C1{slash}SDIO_D6-Pad63)") (class "Default")
      (node (ref "U2") (pin "63") (pinfunction "PC6/I2S2_MCK/T8C1/T3C1/SDIO_D6_63") (pintype "passive"))
    )
    (net (code "91") (name "unconnected-(U2-PC7{slash}I2S3_MCK{slash}T8C2{slash}T3C2{slash}SDIO_D7-Pad64)") (class "Default")
      (node (ref "U2") (pin "64") (pinfunction "PC7/I2S3_MCK/T8C2/T3C2/SDIO_D7_64") (pintype "passive"))
    )
    (net (code "92") (name "unconnected-(U2-PC8{slash}T8C3{slash}T3C3{slash}SDIO_D0-Pad65)") (class "Default")
      (node (ref "U2") (pin "65") (pinfunction "PC8/T8C3/T3C3/SDIO_D0_65") (pintype "passive"))
    )
    (net (code "93") (name "unconnected-(U2-PC9{slash}T8C4{slash}T3C4{slash}SDIO_D1-Pad66)") (class "Default")
      (node (ref "U2") (pin "66") (pinfunction "PC9/T8C4/T3C4/SDIO_D1_66") (pintype "passive"))
    )
    (net (code "94") (name "unconnected-(U2-PC13-TAMPER-RTC-Pad7)") (class "Default")
      (node (ref "U2") (pin "7") (pinfunction "PC13-TAMPER-RTC_7") (pintype "passive"))
    )
    (net (code "95") (name "unconnected-(U2-PC14-OSC32_IN-Pad8)") (class "Default")
      (node (ref "U2") (pin "8") (pinfunction "PC14-OSC32_IN_8") (pintype "passive"))
    )
    (net (code "96") (name "unconnected-(U2-PC15-OSC32_OUT-Pad9)") (class "Default")
      (node (ref "U2") (pin "9") (pinfunction "PC15-OSC32_OUT_9") (pintype "passive"))
    )
    (net (code "97") (name "unconnected-(U2-PD0{slash}CAN_Rx{slash}FSMC_D2-Pad81)") (class "Default")
      (node (ref "U2") (pin "81") (pinfunction "PD0/CAN_Rx/FSMC_D2_81") (pintype "passive"))
    )
    (net (code "98") (name "unconnected-(U2-PD1{slash}CAN_Tx{slash}FSMC_D3-Pad82)") (class "Default")
      (node (ref "U2") (pin "82") (pinfunction "PD1/CAN_Tx/FSMC_D3_82") (pintype "passive"))
    )
    (net (code "99") (name "unconnected-(U2-PD3{slash}FSMC_CLK-Pad84)") (class "Default")
      (node (ref "U2") (pin "84") (pinfunction "PD3/FSMC_CLK_84") (pintype "passive"))
    )
    (net (code "100") (name "unconnected-(U2-PD4{slash}FSMC_NOE-Pad85)") (class "Default")
      (node (ref "U2") (pin "85") (pinfunction "PD4/FSMC_NOE_85") (pintype "passive"))
    )
    (net (code "101") (name "unconnected-(U2-PD7{slash}FSMC_NE1{slash}FSMC_NCE2-Pad88)") (class "Default")
      (node (ref "U2") (pin "88") (pinfunction "PD7/FSMC_NE1/FSMC_NCE2_88") (pintype "passive"))
    )
    (net (code "102") (name "unconnected-(U2-PD8{slash}USART3_Tx{slash}FSMC_D13-Pad55)") (class "Default")
      (node (ref "U2") (pin "55") (pinfunction "PD8/USART3_Tx/FSMC_D13_55") (pintype "passive"))
    )
    (net (code "103") (name "unconnected-(U2-PD9{slash}USART3_Rx{slash}FSMC_D14-Pad56)") (class "Default")
      (node (ref "U2") (pin "56") (pinfunction "PD9/USART3_Rx/FSMC_D14_56") (pintype "passive"))
    )
    (net (code "104") (name "unconnected-(U2-PD10{slash}FSMC_D15-Pad57)") (class "Default")
      (node (ref "U2") (pin "57") (pinfunction "PD10/FSMC_D15_57") (pintype "passive"))
    )
    (net (code "105") (name "unconnected-(U2-PD11{slash}FSMC_A16-Pad58)") (class "Default")
      (node (ref "U2") (pin "58") (pinfunction "PD11/FSMC_A16_58") (pintype "passive"))
    )
    (net (code "106") (name "unconnected-(U2-PD12{slash}T4C1{slash}FSMC_A17-Pad59)") (class "Default")
      (node (ref "U2") (pin "59") (pinfunction "PD12/T4C1/FSMC_A17_59") (pintype "passive"))
    )
    (net (code "107") (name "unconnected-(U2-PD13{slash}T4C2{slash}FSMC_A18-Pad60)") (class "Default")
      (node (ref "U2") (pin "60") (pinfunction "PD13/T4C2/FSMC_A18_60") (pintype "passive"))
    )
    (net (code "108") (name "unconnected-(U2-PD14{slash}T4C3{slash}FSMC_D0-Pad61)") (class "Default")
      (node (ref "U2") (pin "61") (pinfunction "PD14/T4C3/FSMC_D0_61") (pintype "passive"))
    )
    (net (code "109") (name "unconnected-(U2-PD15{slash}T4C4{slash}FSMC_D1-Pad62)") (class "Default")
      (node (ref "U2") (pin "62") (pinfunction "PD15/T4C4/FSMC_D1_62") (pintype "passive"))
    )
    (net (code "110") (name "unconnected-(U2-PDR_ON-Pad99)") (class "Default")
      (node (ref "U2") (pin "99") (pinfunction "PDR_ON_99") (pintype "passive"))
    )
    (net (code "111") (name "unconnected-(U2-PE0{slash}T4_ETR{slash}FSMC_NBL0-Pad97)") (class "Default")
      (node (ref "U2") (pin "97") (pinfunction "PE0/T4_ETR/FSMC_NBL0_97") (pintype "passive"))
    )
    (net (code "112") (name "unconnected-(U2-PE1{slash}FSMC_NBL1-Pad98)") (class "Default")
      (node (ref "U2") (pin "98") (pinfunction "PE1/FSMC_NBL1_98") (pintype "passive"))
    )
    (net (code "113") (name "unconnected-(U2-PE3{slash}TRACED0{slash}FSMC_A19-Pad2)") (class "Default")
      (node (ref "U2") (pin "2") (pinfunction "PE3/TRACED0/FSMC_A19_2") (pintype "passive"))
    )
    (net (code "114") (name "unconnected-(U2-PE5{slash}TRACED2{slash}FSMC_A21-Pad4)") (class "Default")
      (node (ref "U2") (pin "4") (pinfunction "PE5/TRACED2/FSMC_A21_4") (pintype "passive"))
    )
    (net (code "115") (name "unconnected-(U2-PE6{slash}TRACED3{slash}FSMC_A22-Pad5)") (class "Default")
      (node (ref "U2") (pin "5") (pinfunction "PE6/TRACED3/FSMC_A22_5") (pintype "passive"))
    )
    (net (code "116") (name "unconnected-(U2-PE13{slash}FSMC_D10{slash}T1C3-Pad44)") (class "Default")
      (node (ref "U2") (pin "44") (pinfunction "PE13/FSMC_D10/T1C3_44") (pintype "passive"))
    )
    (net (code "117") (name "unconnected-(U2-PE14{slash}FSMC_D11{slash}T1C4-Pad45)") (class "Default")
      (node (ref "U2") (pin "45") (pinfunction "PE14/FSMC_D11/T1C4_45") (pintype "passive"))
    )
    (net (code "118") (name "unconnected-(U2-PE15{slash}FSMC_D12{slash}T1BKIN-Pad46)") (class "Default")
      (node (ref "U2") (pin "46") (pinfunction "PE15/FSMC_D12/T1BKIN_46") (pintype "passive"))
    )
    (net (code "119") (name "unconnected-(U6-5R-Pad5)") (class "Default")
      (node (ref "U6") (pin "5") (pinfunction "5R_5") (pintype "passive"))
    )
    (net (code "120") (name "unconnected-(U6-6R-Pad6)") (class "Default")
      (node (ref "U6") (pin "6") (pinfunction "6R_6") (pintype "passive"))
    )
    (net (code "121") (name "unconnected-(U6-7R-Pad7)") (class "Default")
      (node (ref "U6") (pin "7") (pinfunction "7R_7") (pintype "passive"))
    )
    (net (code "122") (name "unconnected-(U6-Q5-Pad12)") (class "Default")
      (node (ref "U6") (pin "12") (pinfunction "Q5_12") (pintype "passive"))
    )
    (net (code "123") (name "unconnected-(U6-Q6-Pad11)") (class "Default")
      (node (ref "U6") (pin "11") (pinfunction "Q6_11") (pintype "passive"))
    )
    (net (code "124") (name "unconnected-(U6-Q7-Pad10)") (class "Default")
      (node (ref "U6") (pin "10") (pinfunction "Q7_10") (pintype "passive"))
    )
  )
)
